# transmitter.net
KiCad netlist of a schematic drawn in Altium Designer
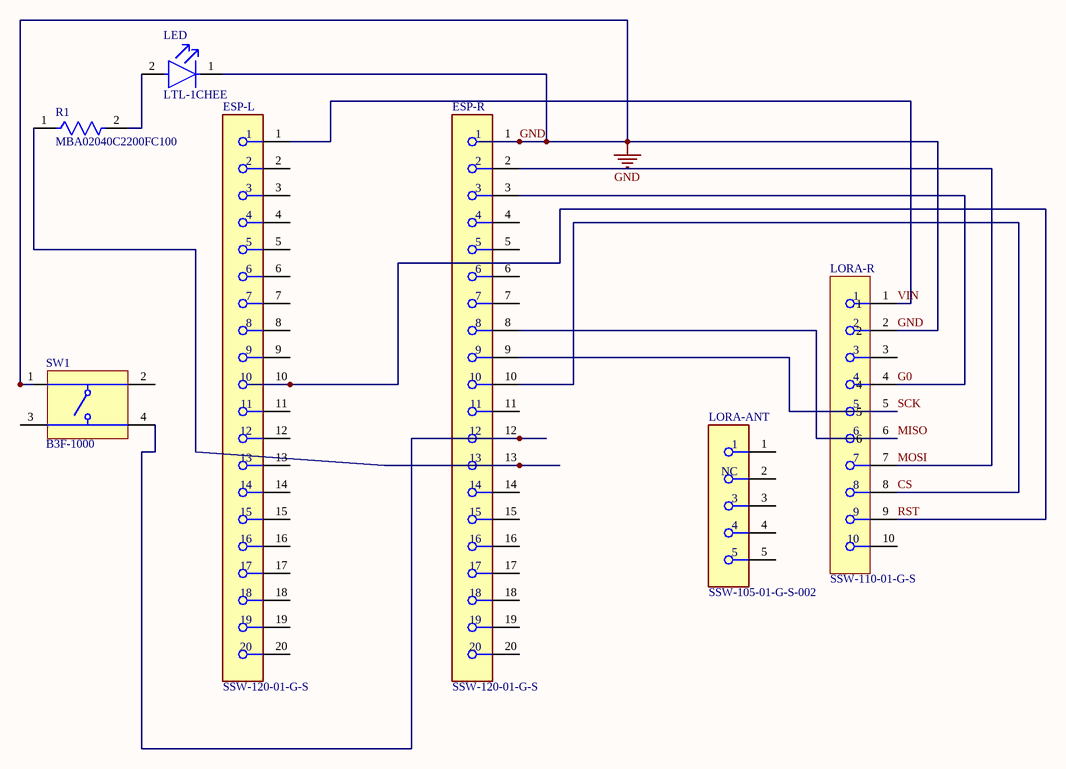
[diagram p0: transmitter.SchDoc]

(export (version "E")
  (design (tool "Eeschema 10.0.6"))
  (components
    (comp (ref "ESP-L")
      (value "SSW-120-01-G-S")
      (footprint "FP-SSW-120-01-G-S-MFG")
      (description "SSW-120-01-G-S SSW - Samtec 2.54mm Single Row Straight Socket Strip 8.5 Profile (mcv)(TO22)")
      (libsource (lib "Altium Content Vault") (part "dba14e038e6f7492952b7f1e871f183"))
    )
    (comp (ref "ESP-R")
      (value "SSW-120-01-G-S")
      (footprint "FP-SSW-120-01-G-S-MFG")
      (description "SSW-120-01-G-S SSW - Samtec 2.54mm Single Row Straight Socket Strip 8.5 Profile (mcv)(TO22)")
      (libsource (lib "Altium Content Vault") (part "dba14e038e6f7492952b7f1e871f183"))
    )
    (comp (ref "LED")
      (value "LTL-1CHEE")
      (footprint "FP-LTL-1CHEE-MFG")
      (description "LED RED CLEAR T/H")
      (libsource (lib "Altium Content Vault") (part "8706943c75ba83719d021d2fdc84c58"))
    )
    (comp (ref "LORA-ANT")
      (value "SSW-105-01-G-S-002")
      (footprint "FP-SSW-105-01-G-S-002-MFG")
      (description "CONN RCPT 5POS 0.1 GOLD PCB")
      (fields
        (field (name "OCTOPART") "https://octopart.com/ssw-105-01-g-s-002-samtec-17275695")
        (field (name "MANUFACTURER") "Samtec")
      )
      (libsource (lib "Altium Content Vault") (part "983be75d0d48fdddaa0c0ee7a70df29"))
    )
    (comp (ref "LORA-R")
      (value "SSW-110-01-G-S")
      (footprint "FP-SSW-110-01-G-S-MFG")
      (libsource (lib "Altium Content Vault") (part "a6b0ccc4a6f32c6729440d11cede569"))
    )
    (comp (ref "R1")
      (value "MBA02040C2200FC100")
      (footprint "FP-MBA0204-MFG")
      (description "RES 220 OHM 0.4W 1% AXIAL")
      (fields
        (field (name "OCTOPART") "https://octopart.com/mba02040c2200fc100-vishay-43743094")
        (field (name "MANUFACTURER") "Vishay BC Components")
      )
      (libsource (lib "Altium Content Vault") (part "1029c3af85768c4190bb7ad29bc67b5"))
    )
    (comp (ref "SW1")
      (value "B3F-1000")
      (footprint "OMRON-B3F-1000-4_V")
      (description "Tactile Switch, SPST-NO, 0.05 A, 5 to 24 V, -25 to 70 degC, 4-Pin THD, RoHS, Bulk")
      (libsource (lib "Altium Content Vault") (part "SW-SPST-4_A"))
    )
  )
  (nets
    (net (code "1") (name "/CS") (class "Default")
      (node (ref "ESP-R") (pin "10") (pinfunction "10_10") (pintype "passive"))
      (node (ref "LORA-R") (pin "8") (pinfunction "8_8") (pintype "passive"))
    )
    (net (code "2") (name "/G0") (class "Default")
      (node (ref "ESP-R") (pin "3") (pinfunction "3_3") (pintype "passive"))
      (node (ref "LORA-R") (pin "4") (pinfunction "4_4") (pintype "passive"))
    )
    (net (code "3") (name "/MISO") (class "Default")
      (node (ref "ESP-R") (pin "8") (pinfunction "8_8") (pintype "passive"))
      (node (ref "LORA-R") (pin "6") (pinfunction "6_6") (pintype "passive"))
    )
    (net (code "4") (name "/MOSI") (class "Default")
      (node (ref "ESP-R") (pin "2") (pinfunction "2_2") (pintype "passive"))
      (node (ref "LORA-R") (pin "7") (pinfunction "7_7") (pintype "passive"))
    )
    (net (code "5") (name "/RST") (class "Default")
      (node (ref "ESP-L") (pin "10") (pinfunction "10_10") (pintype "passive"))
      (node (ref "LORA-R") (pin "9") (pinfunction "9_9") (pintype "passive"))
    )
    (net (code "6") (name "/SCK") (class "Default")
      (node (ref "ESP-R") (pin "9") (pinfunction "9_9") (pintype "passive"))
      (node (ref "LORA-R") (pin "5") (pinfunction "5_5") (pintype "passive"))
    )
    (net (code "7") (name "/VIN") (class "Default")
      (node (ref "ESP-L") (pin "1") (pinfunction "1_1") (pintype "passive"))
      (node (ref "LORA-R") (pin "1") (pinfunction "1_1") (pintype "passive"))
    )
    (net (code "8") (name "GND") (class "Default")
      (node (ref "ESP-R") (pin "1") (pinfunction "1_1") (pintype "passive"))
      (node (ref "LED") (pin "1") (pinfunction "C_1") (pintype "passive"))
      (node (ref "LORA-R") (pin "2") (pinfunction "2_2") (pintype "passive"))
      (node (ref "SW1") (pin "1") (pinfunction "1_1") (pintype "passive"))
    )
    (net (code "9") (name "Net-(ESP-R-Pad12)") (class "Default")
      (node (ref "ESP-R") (pin "12") (pinfunction "12_12") (pintype "passive"))
      (node (ref "SW1") (pin "4") (pinfunction "4_4") (pintype "passive"))
    )
    (net (code "10") (name "Net-(ESP-R-Pad13)") (class "Default")
      (node (ref "ESP-R") (pin "13") (pinfunction "13_13") (pintype "passive"))
      (node (ref "R1") (pin "1") (pinfunction "1_1") (pintype "passive"))
    )
    (net (code "11") (name "Net-(LED-A)") (class "Default")
      (node (ref "LED") (pin "2") (pinfunction "A_2") (pintype "passive"))
      (node (ref "R1") (pin "2") (pinfunction "2_2") (pintype "passive"))
    )
    (net (code "12") (name "unconnected-(ESP-L-Pad2)") (class "Default")
      (node (ref "ESP-L") (pin "2") (pinfunction "2_2") (pintype "passive"))
    )
    (net (code "13") (name "unconnected-(ESP-L-Pad3)") (class "Default")
      (node (ref "ESP-L") (pin "3") (pinfunction "3_3") (pintype "passive"))
    )
    (net (code "14") (name "unconnected-(ESP-L-Pad4)") (class "Default")
      (node (ref "ESP-L") (pin "4") (pinfunction "4_4") (pintype "passive"))
    )
    (net (code "15") (name "unconnected-(ESP-L-Pad5)") (class "Default")
      (node (ref "ESP-L") (pin "5") (pinfunction "5_5") (pintype "passive"))
    )
    (net (code "16") (name "unconnected-(ESP-L-Pad6)") (class "Default")
      (node (ref "ESP-L") (pin "6") (pinfunction "6_6") (pintype "passive"))
    )
    (net (code "17") (name "unconnected-(ESP-L-Pad7)") (class "Default")
      (node (ref "ESP-L") (pin "7") (pinfunction "7_7") (pintype "passive"))
    )
    (net (code "18") (name "unconnected-(ESP-L-Pad8)") (class "Default")
      (node (ref "ESP-L") (pin "8") (pinfunction "8_8") (pintype "passive"))
    )
    (net (code "19") (name "unconnected-(ESP-L-Pad9)") (class "Default")
      (node (ref "ESP-L") (pin "9") (pinfunction "9_9") (pintype "passive"))
    )
    (net (code "20") (name "unconnected-(ESP-L-Pad11)") (class "Default")
      (node (ref "ESP-L") (pin "11") (pinfunction "11_11") (pintype "passive"))
    )
    (net (code "21") (name "unconnected-(ESP-L-Pad12)") (class "Default")
      (node (ref "ESP-L") (pin "12") (pinfunction "12_12") (pintype "passive"))
    )
    (net (code "22") (name "unconnected-(ESP-L-Pad13)") (class "Default")
      (node (ref "ESP-L") (pin "13") (pinfunction "13_13") (pintype "passive"))
    )
    (net (code "23") (name "unconnected-(ESP-L-Pad14)") (class "Default")
      (node (ref "ESP-L") (pin "14") (pinfunction "14_14") (pintype "passive"))
    )
    (net (code "24") (name "unconnected-(ESP-L-Pad15)") (class "Default")
      (node (ref "ESP-L") (pin "15") (pinfunction "15_15") (pintype "passive"))
    )
    (net (code "25") (name "unconnected-(ESP-L-Pad16)") (class "Default")
      (node (ref "ESP-L") (pin "16") (pinfunction "16_16") (pintype "passive"))
    )
    (net (code "26") (name "unconnected-(ESP-L-Pad17)") (class "Default")
      (node (ref "ESP-L") (pin "17") (pinfunction "17_17") (pintype "passive"))
    )
    (net (code "27") (name "unconnected-(ESP-L-Pad18)") (class "Default")
      (node (ref "ESP-L") (pin "18") (pinfunction "18_18") (pintype "passive"))
    )
    (net (code "28") (name "unconnected-(ESP-L-Pad19)") (class "Default")
      (node (ref "ESP-L") (pin "19") (pinfunction "19_19") (pintype "passive"))
    )
    (net (code "29") (name "unconnected-(ESP-L-Pad20)") (class "Default")
      (node (ref "ESP-L") (pin "20") (pinfunction "20_20") (pintype "passive"))
    )
    (net (code "30") (name "unconnected-(ESP-R-Pad4)") (class "Default")
      (node (ref "ESP-R") (pin "4") (pinfunction "4_4") (pintype "passive"))
    )
    (net (code "31") (name "unconnected-(ESP-R-Pad5)") (class "Default")
      (node (ref "ESP-R") (pin "5") (pinfunction "5_5") (pintype "passive"))
    )
    (net (code "32") (name "unconnected-(ESP-R-Pad6)") (class "Default")
      (node (ref "ESP-R") (pin "6") (pinfunction "6_6") (pintype "passive"))
    )
    (net (code "33") (name "unconnected-(ESP-R-Pad7)") (class "Default")
      (node (ref "ESP-R") (pin "7") (pinfunction "7_7") (pintype "passive"))
    )
    (net (code "34") (name "unconnected-(ESP-R-Pad11)") (class "Default")
      (node (ref "ESP-R") (pin "11") (pinfunction "11_11") (pintype "passive"))
    )
    (net (code "35") (name "unconnected-(ESP-R-Pad14)") (class "Default")
      (node (ref "ESP-R") (pin "14") (pinfunction "14_14") (pintype "passive"))
    )
    (net (code "36") (name "unconnected-(ESP-R-Pad15)") (class "Default")
      (node (ref "ESP-R") (pin "15") (pinfunction "15_15") (pintype "passive"))
    )
    (net (code "37") (name "unconnected-(ESP-R-Pad16)") (class "Default")
      (node (ref "ESP-R") (pin "16") (pinfunction "16_16") (pintype "passive"))
    )
    (net (code "38") (name "unconnected-(ESP-R-Pad17)") (class "Default")
      (node (ref "ESP-R") (pin "17") (pinfunction "17_17") (pintype "passive"))
    )
    (net (code "39") (name "unconnected-(ESP-R-Pad18)") (class "Default")
      (node (ref "ESP-R") (pin "18") (pinfunction "18_18") (pintype "passive"))
    )
    (net (code "40") (name "unconnected-(ESP-R-Pad19)") (class "Default")
      (node (ref "ESP-R") (pin "19") (pinfunction "19_19") (pintype "passive"))
    )
    (net (code "41") (name "unconnected-(ESP-R-Pad20)") (class "Default")
      (node (ref "ESP-R") (pin "20") (pinfunction "20_20") (pintype "passive"))
    )
    (net (code "42") (name "unconnected-(LORA-ANT-NC-Pad2)") (class "Default")
      (node (ref "LORA-ANT") (pin "2") (pinfunction "NC_2") (pintype "passive"))
    )
    (net (code "43") (name "unconnected-(LORA-ANT-Pad1)") (class "Default")
      (node (ref "LORA-ANT") (pin "1") (pinfunction "1_1") (pintype "passive"))
    )
    (net (code "44") (name "unconnected-(LORA-ANT-Pad3)") (class "Default")
      (node (ref "LORA-ANT") (pin "3") (pinfunction "3_3") (pintype "passive"))
    )
    (net (code "45") (name "unconnected-(LORA-ANT-Pad4)") (class "Default")
      (node (ref "LORA-ANT") (pin "4") (pinfunction "4_4") (pintype "passive"))
    )
    (net (code "46") (name "unconnected-(LORA-ANT-Pad5)") (class "Default")
      (node (ref "LORA-ANT") (pin "5") (pinfunction "5_5") (pintype "passive"))
    )
    (net (code "47") (name "unconnected-(LORA-R-Pad3)") (class "Default")
      (node (ref "LORA-R") (pin "3") (pinfunction "3_3") (pintype "passive"))
    )
    (net (code "48") (name "unconnected-(LORA-R-Pad10)") (class "Default")
      (node (ref "LORA-R") (pin "10") (pinfunction "10_10") (pintype "passive"))
    )
    (net (code "49") (name "unconnected-(SW1-Pad2)") (class "Default")
      (node (ref "SW1") (pin "2") (pinfunction "2_2") (pintype "passive"))
    )
    (net (code "50") (name "unconnected-(SW1-Pad3)") (class "Default")
      (node (ref "SW1") (pin "3") (pinfunction "3_3") (pintype "passive"))
    )
  )
)
